# Design.net
KiCad netlist of a schematic drawn in EAGLE
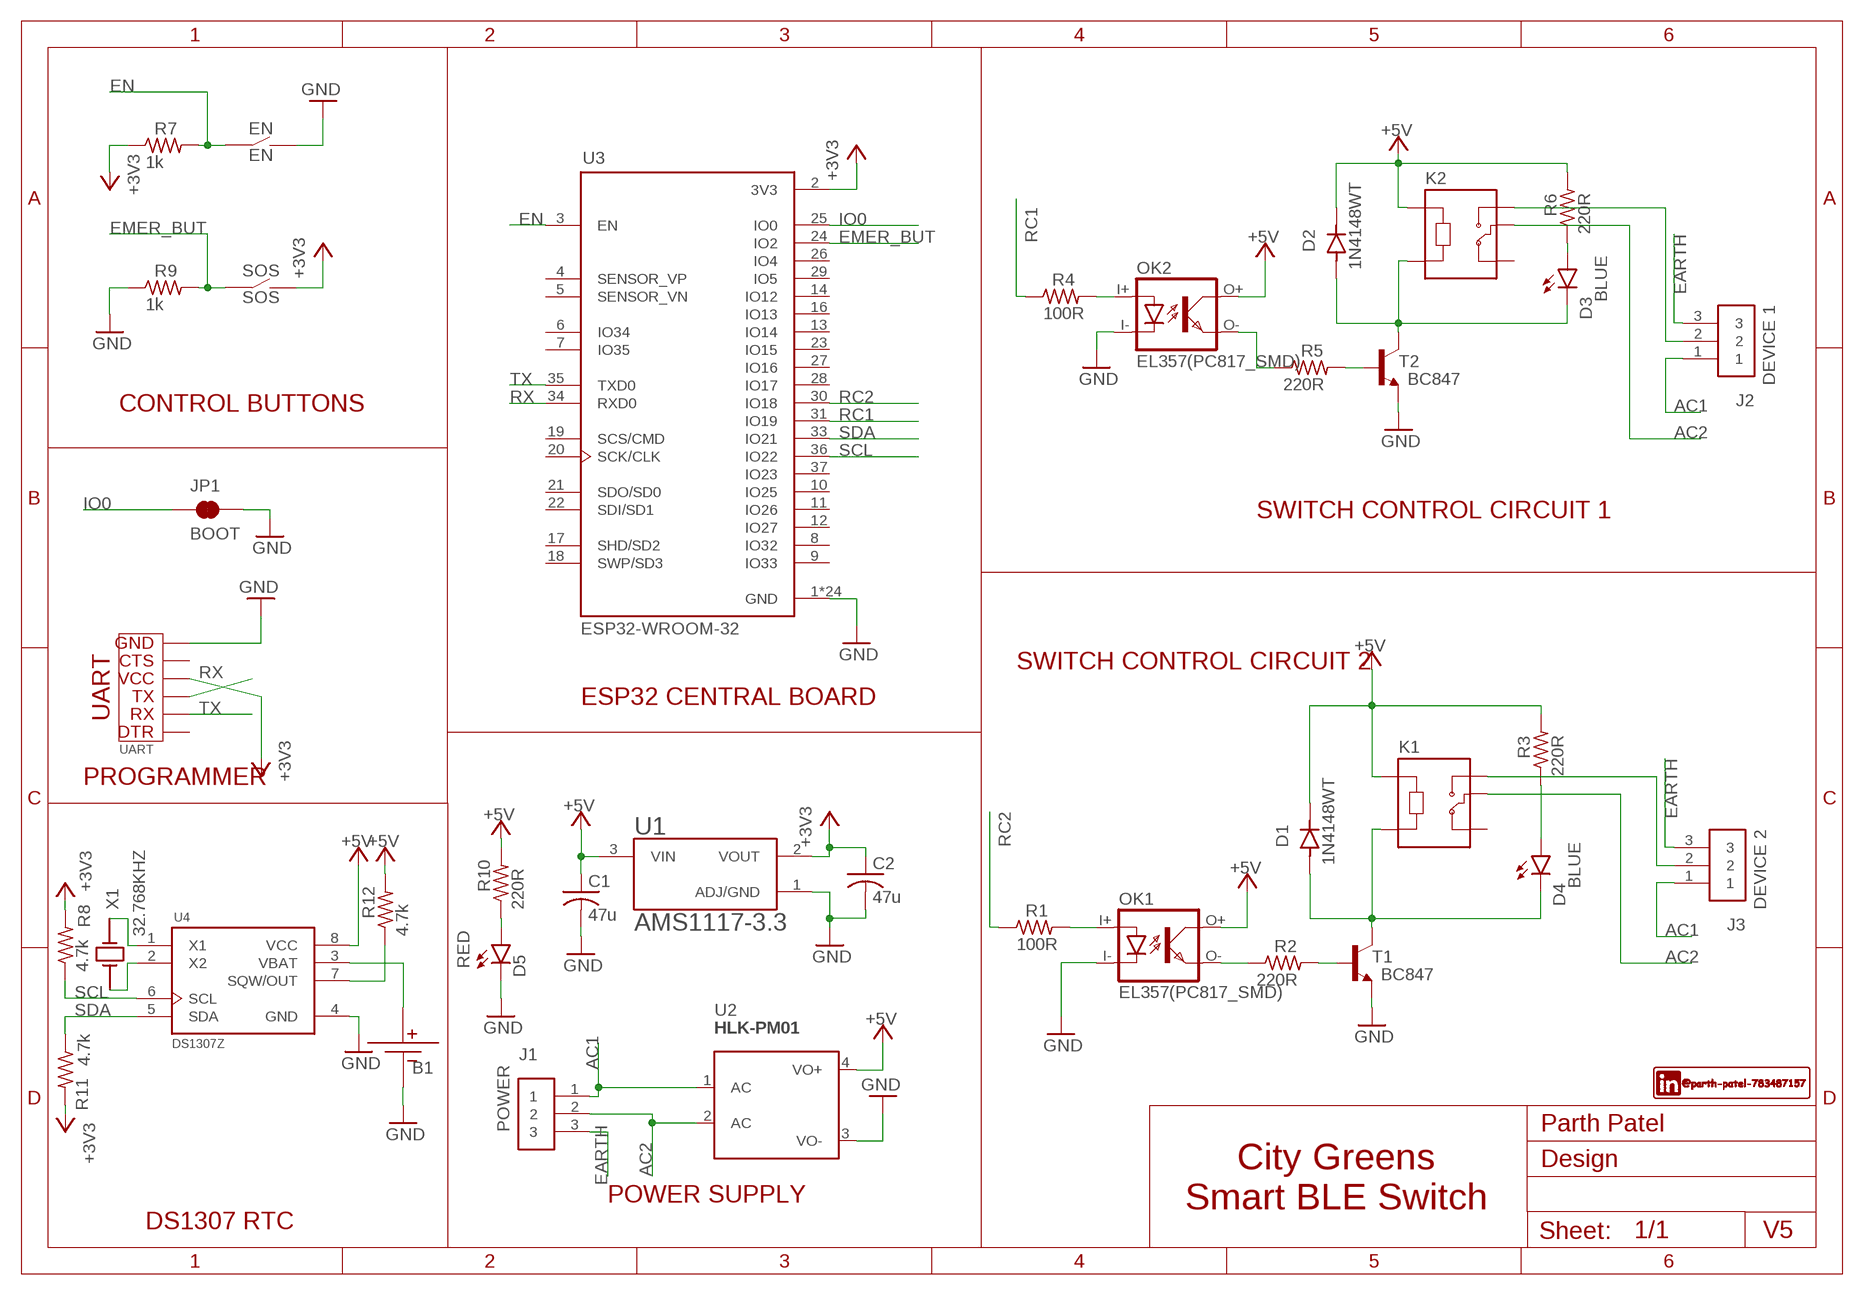
[diagram p0: schematic, sheet 1]

(export (version "E")
  (design (tool "Eeschema 10.0.6"))
  (components
    (comp (ref "B1")
      (value "CR3032-METAL")
      (footprint "eagle-import:CR2032-METAL")
      (libsource (lib "eagle-import") (part "CR3032-METAL"))
    )
    (comp (ref "C1")
      (value "47u")
      (footprint "eagle-import:C0805")
      (libsource (lib "eagle-import") (part "C-USC0805"))
    )
    (comp (ref "C2")
      (value "47u")
      (footprint "eagle-import:C0805")
      (libsource (lib "eagle-import") (part "C-USC0805"))
    )
    (comp (ref "D1")
      (value "1N4148WT")
      (footprint "eagle-import:SODFL1608X70N")
      (libsource (lib "eagle-import") (part "1N4148WT"))
    )
    (comp (ref "D2")
      (value "1N4148WT")
      (footprint "eagle-import:SODFL1608X70N")
      (fields (field (name "SPICEPREFIX") "D"))
      (libsource (lib "eagle-import") (part "1N4148WT"))
    )
    (comp (ref "D3")
      (value "BLUE")
      (footprint "eagle-import:CHIP-LED0603")
      (libsource (lib "eagle-import") (part "LEDCHIP-LED0603"))
    )
    (comp (ref "D4")
      (value "BLUE")
      (footprint "eagle-import:CHIP-LED0603")
      (libsource (lib "eagle-import") (part "LEDCHIP-LED0603"))
    )
    (comp (ref "D5")
      (value "RED")
      (footprint "eagle-import:CHIP-LED0603")
      (libsource (lib "eagle-import") (part "LEDCHIP-LED0603"))
    )
    (comp (ref "EN")
      (value "EN")
      (footprint "eagle-import:SMD-4.5X4.5-TACTILE-PUSH-BUTTON")
      (libsource (lib "eagle-import") (part "4.5X4.5-SMD-TACTILE-SWITCH"))
    )
    (comp (ref "J1")
      (value "POWER")
      (footprint "eagle-import:TERMINALBLOCK_PLUGGABLE-3-7.62MM")
      (fields
        (field (name "DIGIKEY_PART_NO") "732-2824-ND")
        (field (name "MANUFACTURER") "WURTH ELEKTRONIK")
        (field (name "MPN") "691311400103")
        (field (name "CREATED_BY") "PCBLayout.com")
      )
      (libsource (lib "eagle-import") (part "691311400103"))
    )
    (comp (ref "J2")
      (value "DEVICE 1")
      (footprint "eagle-import:TERMINALBLOCK_PLUGGABLE-3-7.62MM")
      (fields
        (field (name "DIGIKEY_PART_NO") "732-2824-ND")
        (field (name "MANUFACTURER") "WURTH ELEKTRONIK")
        (field (name "MPN") "691311400103")
        (field (name "CREATED_BY") "PCBLayout.com")
      )
      (libsource (lib "eagle-import") (part "691311400103"))
    )
    (comp (ref "J3")
      (value "DEVICE 2")
      (footprint "eagle-import:TERMINALBLOCK_PLUGGABLE-3-7.62MM")
      (fields
        (field (name "DIGIKEY_PART_NO") "732-2824-ND")
        (field (name "MANUFACTURER") "WURTH ELEKTRONIK")
        (field (name "MPN") "691311400103")
        (field (name "CREATED_BY") "PCBLayout.com")
      )
      (libsource (lib "eagle-import") (part "691311400103"))
    )
    (comp (ref "JP1")
      (value "BOOT")
      (footprint "eagle-import:SMT-JUMPER_2_NC_TRACE_SILK")
      (libsource (lib "eagle-import") (part "JUMPER-SMT_2_NC_TRACE_SILK"))
    )
    (comp (ref "K1")
      (value "SRD-05VDC-SL-C")
      (footprint "eagle-import:RELAY_SRD-05VDC-SL-C")
      (fields (field (name "MF") "Songle Relay"))
      (libsource (lib "eagle-import") (part "SRD-05VDC-SL-C"))
    )
    (comp (ref "K2")
      (value "SRD-05VDC-SL-C")
      (footprint "eagle-import:RELAY_SRD-05VDC-SL-C")
      (fields (field (name "MF") "Songle Relay"))
      (libsource (lib "eagle-import") (part "SRD-05VDC-SL-C"))
    )
    (comp (ref "OK1")
      (value "EL357(PC817_SMD)")
      (footprint "eagle-import:SOP254P715X240-4N")
      (libsource (lib "eagle-import") (part "EL357(PC817_SMD)"))
    )
    (comp (ref "OK2")
      (value "EL357(PC817_SMD)")
      (footprint "eagle-import:SOP254P715X240-4N")
      (libsource (lib "eagle-import") (part "EL357(PC817_SMD)"))
    )
    (comp (ref "R1")
      (value "100R")
      (footprint "eagle-import:R0805")
      (libsource (lib "eagle-import") (part "R-US_R0805"))
    )
    (comp (ref "R2")
      (value "220R")
      (footprint "eagle-import:R0805")
      (libsource (lib "eagle-import") (part "R-US_R0805"))
    )
    (comp (ref "R3")
      (value "220R")
      (footprint "eagle-import:R0805")
      (libsource (lib "eagle-import") (part "R-US_R0805"))
    )
    (comp (ref "R4")
      (value "100R")
      (footprint "eagle-import:R0805")
      (libsource (lib "eagle-import") (part "R-US_R0805"))
    )
    (comp (ref "R5")
      (value "220R")
      (footprint "eagle-import:R0805")
      (libsource (lib "eagle-import") (part "R-US_R0805"))
    )
    (comp (ref "R6")
      (value "220R")
      (footprint "eagle-import:R0805")
      (libsource (lib "eagle-import") (part "R-US_R0805"))
    )
    (comp (ref "R7")
      (value "1k")
      (footprint "eagle-import:R0805")
      (libsource (lib "eagle-import") (part "R-US_R0805"))
    )
    (comp (ref "R8")
      (value "4.7k")
      (footprint "eagle-import:R0805")
      (libsource (lib "eagle-import") (part "R-US_R0805"))
    )
    (comp (ref "R9")
      (value "1k")
      (footprint "eagle-import:R0805")
      (libsource (lib "eagle-import") (part "R-US_R0805"))
    )
    (comp (ref "R10")
      (value "220R")
      (footprint "eagle-import:R0805")
      (libsource (lib "eagle-import") (part "R-US_R0805"))
    )
    (comp (ref "R11")
      (value "4.7k")
      (footprint "eagle-import:R0805")
      (libsource (lib "eagle-import") (part "R-US_R0805"))
    )
    (comp (ref "R12")
      (value "4.7k")
      (footprint "eagle-import:R0805")
      (libsource (lib "eagle-import") (part "R-US_R0805"))
    )
    (comp (ref "SOS")
      (value "SOS")
      (footprint "eagle-import:SMD-4.5X4.5-TACTILE-PUSH-BUTTON")
      (libsource (lib "eagle-import") (part "4.5X4.5-SMD-TACTILE-SWITCH"))
    )
    (comp (ref "T1")
      (value "BC847")
      (footprint "eagle-import:SOT23")
      (libsource (lib "eagle-import") (part "BC847"))
    )
    (comp (ref "T2")
      (value "BC847")
      (footprint "eagle-import:SOT23")
      (libsource (lib "eagle-import") (part "BC847"))
    )
    (comp (ref "U1")
      (value "AMS1117-3.3")
      (footprint "eagle-import:SOT229P700X180-4N")
      (fields (field (name "MF") "AMD"))
      (libsource (lib "eagle-import") (part "AMS1117-3.3"))
    )
    (comp (ref "U2")
      (value "HLK-PM01")
      (footprint "eagle-import:HLK-PM01")
      (fields (field (name "MF") "Hi-link") (field (name "MP") "hlk-pm01"))
      (libsource (lib "eagle-import") (part "HLK-PM01"))
    )
    (comp (ref "U3")
      (value "ESP32-WROOM-32")
      (footprint "eagle-import:MODULE_ESP32-WROOM-32")
      (fields (field (name "MF") "Espressif Systems"))
      (libsource (lib "eagle-import") (part "ESP32-WROOM-32"))
    )
    (comp (ref "U4")
      (value "DS1307Z")
      (footprint "eagle-import:SOIC127P600X175-8N")
      (fields (field (name "MF") "Maxim Integrated"))
      (libsource (lib "eagle-import") (part "DS1307Z"))
    )
    (comp (ref "UART")
      (value "UART")
      (footprint "eagle-import:UART")
      (libsource (lib "eagle-import") (part "UART"))
    )
    (comp (ref "X1")
      (value "32.768KHZ")
      (footprint "eagle-import:XTAL_AB38T-32.768KHZ")
      (fields (field (name "MF") "Abracon") (field (name "MP") "AB38T-32.768KHZ"))
      (libsource (lib "eagle-import") (part "AB38T-32.768KHZ"))
    )
  )
  (nets
    (net (code "1") (name "+3V3") (class "Default")
      (node (ref "C2") (pin "1") (pinfunction "1_1") (pintype "passive"))
      (node (ref "R11") (pin "2") (pinfunction "2_2") (pintype "passive"))
      (node (ref "R7") (pin "1") (pinfunction "1_1") (pintype "passive"))
      (node (ref "R8") (pin "2") (pinfunction "2_2") (pintype "passive"))
      (node (ref "SOS") (pin "2.1") (pinfunction "S2_2.1") (pintype "bidirectional"))
      (node (ref "SOS") (pin "2.2") (pinfunction "S2_2.2") (pintype "bidirectional"))
      (node (ref "U1") (pin "2") (pinfunction "VOUT_2") (pintype "output"))
      (node (ref "U3") (pin "2") (pinfunction "3V3_2") (pintype "power_in"))
      (node (ref "UART") (pin "VCC") (pinfunction "VCC_VCC") (pintype "bidirectional"))
    )
    (net (code "2") (name "+5V") (class "Default")
      (node (ref "C1") (pin "1") (pinfunction "1_1") (pintype "passive"))
      (node (ref "D1") (pin "D+") (pinfunction "D+_D+") (pintype "passive"))
      (node (ref "D2") (pin "D+") (pinfunction "D+_D+") (pintype "passive"))
      (node (ref "K1") (pin "A1") (pinfunction "A1_A1") (pintype "passive"))
      (node (ref "K2") (pin "A1") (pinfunction "A1_A1") (pintype "passive"))
      (node (ref "OK1") (pin "O+") (pinfunction "O+_O+") (pintype "passive"))
      (node (ref "OK2") (pin "O+") (pinfunction "O+_O+") (pintype "passive"))
      (node (ref "R10") (pin "2") (pinfunction "2_2") (pintype "passive"))
      (node (ref "R12") (pin "2") (pinfunction "2_2") (pintype "passive"))
      (node (ref "R3") (pin "2") (pinfunction "2_2") (pintype "passive"))
      (node (ref "R6") (pin "2") (pinfunction "2_2") (pintype "passive"))
      (node (ref "U1") (pin "3") (pinfunction "VIN_3") (pintype "input"))
      (node (ref "U2") (pin "4") (pinfunction "VO+_4") (pintype "bidirectional"))
      (node (ref "U4") (pin "8") (pinfunction "VCC_8") (pintype "power_in"))
    )
    (net (code "3") (name "/AC1") (class "Default")
      (node (ref "J1") (pin "1") (pinfunction "1_1") (pintype "passive"))
      (node (ref "J2") (pin "1") (pinfunction "1_1") (pintype "passive"))
      (node (ref "J3") (pin "1") (pinfunction "1_1") (pintype "passive"))
      (node (ref "U2") (pin "1") (pinfunction "AC_1") (pintype "bidirectional"))
    )
    (net (code "4") (name "/AC2") (class "Default")
      (node (ref "J1") (pin "2") (pinfunction "2_2") (pintype "passive"))
      (node (ref "K1") (pin "COM") (pinfunction "COM_COM") (pintype "passive"))
      (node (ref "K2") (pin "COM") (pinfunction "COM_COM") (pintype "passive"))
      (node (ref "U2") (pin "2") (pinfunction "AC_2") (pintype "bidirectional"))
    )
    (net (code "5") (name "/EARTH") (class "Default")
      (node (ref "J1") (pin "3") (pinfunction "3_3") (pintype "passive"))
      (node (ref "J2") (pin "3") (pinfunction "3_3") (pintype "passive"))
      (node (ref "J3") (pin "3") (pinfunction "3_3") (pintype "passive"))
    )
    (net (code "6") (name "/EMER_BUT") (class "Default")
      (node (ref "R9") (pin "2") (pinfunction "2_2") (pintype "passive"))
      (node (ref "SOS") (pin "1.1") (pinfunction "S1_1.1") (pintype "bidirectional"))
      (node (ref "SOS") (pin "1.2") (pinfunction "S1_1.2") (pintype "bidirectional"))
      (node (ref "U3") (pin "24") (pinfunction "IO2_24") (pintype "bidirectional"))
    )
    (net (code "7") (name "/EN") (class "Default")
      (node (ref "EN") (pin "1.1") (pinfunction "S1_1.1") (pintype "bidirectional"))
      (node (ref "EN") (pin "1.2") (pinfunction "S1_1.2") (pintype "bidirectional"))
      (node (ref "R7") (pin "2") (pinfunction "2_2") (pintype "passive"))
      (node (ref "U3") (pin "3") (pinfunction "EN_3") (pintype "input"))
    )
    (net (code "8") (name "/IO0") (class "Default")
      (node (ref "JP1") (pin "1") (pinfunction "1_1") (pintype "passive"))
      (node (ref "U3") (pin "25") (pinfunction "IO0_25") (pintype "bidirectional"))
    )
    (net (code "9") (name "/RC1") (class "Default")
      (node (ref "R4") (pin "1") (pinfunction "1_1") (pintype "passive"))
      (node (ref "U3") (pin "31") (pinfunction "IO19_31") (pintype "bidirectional"))
    )
    (net (code "10") (name "/RC2") (class "Default")
      (node (ref "R1") (pin "1") (pinfunction "1_1") (pintype "passive"))
      (node (ref "U3") (pin "30") (pinfunction "IO18_30") (pintype "bidirectional"))
    )
    (net (code "11") (name "/RX") (class "Default")
      (node (ref "U3") (pin "34") (pinfunction "RXD0_34") (pintype "bidirectional"))
      (node (ref "UART") (pin "TX") (pinfunction "TX_TX") (pintype "bidirectional"))
    )
    (net (code "12") (name "/SCL") (class "Default")
      (node (ref "R8") (pin "1") (pinfunction "1_1") (pintype "passive"))
      (node (ref "U3") (pin "36") (pinfunction "IO22_36") (pintype "bidirectional"))
      (node (ref "U4") (pin "6") (pinfunction "SCL_6") (pintype "input"))
    )
    (net (code "13") (name "/SDA") (class "Default")
      (node (ref "R11") (pin "1") (pinfunction "1_1") (pintype "passive"))
      (node (ref "U3") (pin "33") (pinfunction "IO21_33") (pintype "bidirectional"))
      (node (ref "U4") (pin "5") (pinfunction "SDA_5") (pintype "bidirectional"))
    )
    (net (code "14") (name "/TX") (class "Default")
      (node (ref "U3") (pin "35") (pinfunction "TXD0_35") (pintype "bidirectional"))
      (node (ref "UART") (pin "RX") (pinfunction "RX_RX") (pintype "bidirectional"))
    )
    (net (code "15") (name "GND") (class "Default")
      (node (ref "B1") (pin "-VE1") (pinfunction "-VE_-VE1") (pintype "bidirectional"))
      (node (ref "B1") (pin "-VE2") (pinfunction "-VE_-VE2") (pintype "bidirectional"))
      (node (ref "C1") (pin "2") (pinfunction "2_2") (pintype "passive"))
      (node (ref "C2") (pin "2") (pinfunction "2_2") (pintype "passive"))
      (node (ref "D5") (pin "C") (pinfunction "C_C") (pintype "passive"))
      (node (ref "EN") (pin "2.1") (pinfunction "S2_2.1") (pintype "bidirectional"))
      (node (ref "EN") (pin "2.2") (pinfunction "S2_2.2") (pintype "bidirectional"))
      (node (ref "JP1") (pin "2") (pinfunction "2_2") (pintype "passive"))
      (node (ref "OK1") (pin "I-") (pinfunction "I-_I-") (pintype "passive"))
      (node (ref "OK2") (pin "I-") (pinfunction "I-_I-") (pintype "passive"))
      (node (ref "R9") (pin "1") (pinfunction "1_1") (pintype "passive"))
      (node (ref "T1") (pin "2") (pinfunction "E_2") (pintype "passive"))
      (node (ref "T2") (pin "2") (pinfunction "E_2") (pintype "passive"))
      (node (ref "U1") (pin "1") (pinfunction "ADJ/GND_1") (pintype "power_in"))
      (node (ref "U2") (pin "3") (pinfunction "VO-_3") (pintype "bidirectional"))
      (node (ref "U3") (pin "1") (pinfunction "GND_1") (pintype "power_in"))
      (node (ref "U3") (pin "15") (pinfunction "GND_15") (pintype "power_in"))
      (node (ref "U3") (pin "38") (pinfunction "GND_38") (pintype "power_in"))
      (node (ref "U3") (pin "39_1") (pinfunction "GND_39_1") (pintype "power_in"))
      (node (ref "U3") (pin "39_10") (pinfunction "GND_39_10") (pintype "power_in"))
      (node (ref "U3") (pin "39_11") (pinfunction "GND_39_11") (pintype "power_in"))
      (node (ref "U3") (pin "39_12") (pinfunction "GND_39_12") (pintype "power_in"))
      (node (ref "U3") (pin "39_13") (pinfunction "GND_39_13") (pintype "power_in"))
      (node (ref "U3") (pin "39_14") (pinfunction "GND_39_14") (pintype "power_in"))
      (node (ref "U3") (pin "39_15") (pinfunction "GND_39_15") (pintype "power_in"))
      (node (ref "U3") (pin "39_16") (pinfunction "GND_39_16") (pintype "power_in"))
      (node (ref "U3") (pin "39_17") (pinfunction "GND_39_17") (pintype "power_in"))
      (node (ref "U3") (pin "39_18") (pinfunction "GND_39_18") (pintype "power_in"))
      (node (ref "U3") (pin "39_19") (pinfunction "GND_39_19") (pintype "power_in"))
      (node (ref "U3") (pin "39_2") (pinfunction "GND_39_2") (pintype "power_in"))
      (node (ref "U3") (pin "39_20") (pinfunction "GND_39_20") (pintype "power_in"))
      (node (ref "U3") (pin "39_21") (pinfunction "GND_39_21") (pintype "power_in"))
      (node (ref "U3") (pin "39_3") (pinfunction "GND_39_3") (pintype "power_in"))
      (node (ref "U3") (pin "39_4") (pinfunction "GND_39_4") (pintype "power_in"))
      (node (ref "U3") (pin "39_5") (pinfunction "GND_39_5") (pintype "power_in"))
      (node (ref "U3") (pin "39_6") (pinfunction "GND_39_6") (pintype "power_in"))
      (node (ref "U3") (pin "39_7") (pinfunction "GND_39_7") (pintype "power_in"))
      (node (ref "U3") (pin "39_8") (pinfunction "GND_39_8") (pintype "power_in"))
      (node (ref "U3") (pin "39_9") (pinfunction "GND_39_9") (pintype "power_in"))
      (node (ref "U4") (pin "4") (pinfunction "GND_4") (pintype "power_in"))
      (node (ref "UART") (pin "GND") (pinfunction "GND_GND") (pintype "bidirectional"))
    )
    (net (code "16") (name "Net-(D3-PadA)") (class "Default")
      (node (ref "D3") (pin "A") (pinfunction "A_A") (pintype "passive"))
      (node (ref "R6") (pin "1") (pinfunction "1_1") (pintype "passive"))
    )
    (net (code "17") (name "Net-(D4-PadA)") (class "Default")
      (node (ref "D4") (pin "A") (pinfunction "A_A") (pintype "passive"))
      (node (ref "R3") (pin "1") (pinfunction "1_1") (pintype "passive"))
    )
    (net (code "18") (name "Net-(D5-PadA)") (class "Default")
      (node (ref "D5") (pin "A") (pinfunction "A_A") (pintype "passive"))
      (node (ref "R10") (pin "1") (pinfunction "1_1") (pintype "passive"))
    )
    (net (code "19") (name "Net-(J2-Pad2)") (class "Default")
      (node (ref "J2") (pin "2") (pinfunction "2_2") (pintype "passive"))
      (node (ref "K2") (pin "NO") (pinfunction "NO_NO") (pintype "passive"))
    )
    (net (code "20") (name "Net-(J3-Pad2)") (class "Default")
      (node (ref "J3") (pin "2") (pinfunction "2_2") (pintype "passive"))
      (node (ref "K1") (pin "NO") (pinfunction "NO_NO") (pintype "passive"))
    )
    (net (code "21") (name "Net-(OK1-PadI+)") (class "Default")
      (node (ref "OK1") (pin "I+") (pinfunction "I+_I+") (pintype "passive"))
      (node (ref "R1") (pin "2") (pinfunction "2_2") (pintype "passive"))
    )
    (net (code "22") (name "Net-(OK1-PadO-)") (class "Default")
      (node (ref "OK1") (pin "O-") (pinfunction "O-_O-") (pintype "passive"))
      (node (ref "R2") (pin "1") (pinfunction "1_1") (pintype "passive"))
    )
    (net (code "23") (name "Net-(OK2-PadI+)") (class "Default")
      (node (ref "OK2") (pin "I+") (pinfunction "I+_I+") (pintype "passive"))
      (node (ref "R4") (pin "2") (pinfunction "2_2") (pintype "passive"))
    )
    (net (code "24") (name "Net-(OK2-PadO-)") (class "Default")
      (node (ref "OK2") (pin "O-") (pinfunction "O-_O-") (pintype "passive"))
      (node (ref "R5") (pin "1") (pinfunction "1_1") (pintype "passive"))
    )
    (net (code "25") (name "Net-(T1-B)") (class "Default")
      (node (ref "R2") (pin "2") (pinfunction "2_2") (pintype "passive"))
      (node (ref "T1") (pin "1") (pinfunction "B_1") (pintype "passive"))
    )
    (net (code "26") (name "Net-(T1-C)") (class "Default")
      (node (ref "D1") (pin "D-") (pinfunction "D-_D-") (pintype "passive"))
      (node (ref "D4") (pin "C") (pinfunction "C_C") (pintype "passive"))
      (node (ref "K1") (pin "A2") (pinfunction "A2_A2") (pintype "passive"))
      (node (ref "T1") (pin "3") (pinfunction "C_3") (pintype "passive"))
    )
    (net (code "27") (name "Net-(T2-B)") (class "Default")
      (node (ref "R5") (pin "2") (pinfunction "2_2") (pintype "passive"))
      (node (ref "T2") (pin "1") (pinfunction "B_1") (pintype "passive"))
    )
    (net (code "28") (name "Net-(T2-C)") (class "Default")
      (node (ref "D2") (pin "D-") (pinfunction "D-_D-") (pintype "passive"))
      (node (ref "D3") (pin "C") (pinfunction "C_C") (pintype "passive"))
      (node (ref "K2") (pin "A2") (pinfunction "A2_A2") (pintype "passive"))
      (node (ref "T2") (pin "3") (pinfunction "C_3") (pintype "passive"))
    )
    (net (code "29") (name "Net-(U4-SQW{slash}OUT)") (class "Default")
      (node (ref "R12") (pin "1") (pinfunction "1_1") (pintype "passive"))
      (node (ref "U4") (pin "7") (pinfunction "SQW/OUT_7") (pintype "output"))
    )
    (net (code "30") (name "Net-(U4-VBAT)") (class "Default")
      (node (ref "B1") (pin "+VE") (pinfunction "+VE_+VE") (pintype "bidirectional"))
      (node (ref "U4") (pin "3") (pinfunction "VBAT_3") (pintype "power_in"))
    )
    (net (code "31") (name "Net-(U4-X1)") (class "Default")
      (node (ref "U4") (pin "1") (pinfunction "X1_1") (pintype "input"))
      (node (ref "X1") (pin "2") (pinfunction "2_2") (pintype "passive"))
    )
    (net (code "32") (name "Net-(U4-X2)") (class "Default")
      (node (ref "U4") (pin "2") (pinfunction "X2_2") (pintype "input"))
      (node (ref "X1") (pin "1") (pinfunction "1_1") (pintype "passive"))
    )
    (net (code "33") (name "unconnected-(K1-PadNC)") (class "Default")
      (node (ref "K1") (pin "NC") (pinfunction "NC_NC") (pintype "passive"))
    )
    (net (code "34") (name "unconnected-(K2-PadNC)") (class "Default")
      (node (ref "K2") (pin "NC") (pinfunction "NC_NC") (pintype "passive"))
    )
    (net (code "35") (name "unconnected-(U3-IO4-Pad26)") (class "Default")
      (node (ref "U3") (pin "26") (pinfunction "IO4_26") (pintype "bidirectional"))
    )
    (net (code "36") (name "unconnected-(U3-IO5-Pad29)") (class "Default")
      (node (ref "U3") (pin "29") (pinfunction "IO5_29") (pintype "bidirectional"))
    )
    (net (code "37") (name "unconnected-(U3-IO12-Pad14)") (class "Default")
      (node (ref "U3") (pin "14") (pinfunction "IO12_14") (pintype "bidirectional"))
    )
    (net (code "38") (name "unconnected-(U3-IO13-Pad16)") (class "Default")
      (node (ref "U3") (pin "16") (pinfunction "IO13_16") (pintype "bidirectional"))
    )
    (net (code "39") (name "unconnected-(U3-IO14-Pad13)") (class "Default")
      (node (ref "U3") (pin "13") (pinfunction "IO14_13") (pintype "bidirectional"))
    )
    (net (code "40") (name "unconnected-(U3-IO15-Pad23)") (class "Default")
      (node (ref "U3") (pin "23") (pinfunction "IO15_23") (pintype "bidirectional"))
    )
    (net (code "41") (name "unconnected-(U3-IO16-Pad27)") (class "Default")
      (node (ref "U3") (pin "27") (pinfunction "IO16_27") (pintype "bidirectional"))
    )
    (net (code "42") (name "unconnected-(U3-IO17-Pad28)") (class "Default")
      (node (ref "U3") (pin "28") (pinfunction "IO17_28") (pintype "bidirectional"))
    )
    (net (code "43") (name "unconnected-(U3-IO23-Pad37)") (class "Default")
      (node (ref "U3") (pin "37") (pinfunction "IO23_37") (pintype "bidirectional"))
    )
    (net (code "44") (name "unconnected-(U3-IO25-Pad10)") (class "Default")
      (node (ref "U3") (pin "10") (pinfunction "IO25_10") (pintype "bidirectional"))
    )
    (net (code "45") (name "unconnected-(U3-IO26-Pad11)") (class "Default")
      (node (ref "U3") (pin "11") (pinfunction "IO26_11") (pintype "bidirectional"))
    )
    (net (code "46") (name "unconnected-(U3-IO27-Pad12)") (class "Default")
      (node (ref "U3") (pin "12") (pinfunction "IO27_12") (pintype "bidirectional"))
    )
    (net (code "47") (name "unconnected-(U3-IO32-Pad8)") (class "Default")
      (node (ref "U3") (pin "8") (pinfunction "IO32_8") (pintype "bidirectional"))
    )
    (net (code "48") (name "unconnected-(U3-IO33-Pad9)") (class "Default")
      (node (ref "U3") (pin "9") (pinfunction "IO33_9") (pintype "bidirectional"))
    )
    (net (code "49") (name "unconnected-(U3-IO34-Pad6)") (class "Default")
      (node (ref "U3") (pin "6") (pinfunction "IO34_6") (pintype "input"))
    )
    (net (code "50") (name "unconnected-(U3-IO35-Pad7)") (class "Default")
      (node (ref "U3") (pin "7") (pinfunction "IO35_7") (pintype "input"))
    )
    (net (code "51") (name "unconnected-(U3-SCK{slash}CLK-Pad20)") (class "Default")
      (node (ref "U3") (pin "20") (pinfunction "SCK/CLK_20") (pintype "bidirectional"))
    )
    (net (code "52") (name "unconnected-(U3-SCS{slash}CMD-Pad19)") (class "Default")
      (node (ref "U3") (pin "19") (pinfunction "SCS/CMD_19") (pintype "bidirectional"))
    )
    (net (code "53") (name "unconnected-(U3-SDI{slash}SD1-Pad22)") (class "Default")
      (node (ref "U3") (pin "22") (pinfunction "SDI/SD1_22") (pintype "bidirectional"))
    )
    (net (code "54") (name "unconnected-(U3-SDO{slash}SD0-Pad21)") (class "Default")
      (node (ref "U3") (pin "21") (pinfunction "SDO/SD0_21") (pintype "bidirectional"))
    )
    (net (code "55") (name "unconnected-(U3-SENSOR_VN-Pad5)") (class "Default")
      (node (ref "U3") (pin "5") (pinfunction "SENSOR_VN_5") (pintype "input"))
    )
    (net (code "56") (name "unconnected-(U3-SENSOR_VP-Pad4)") (class "Default")
      (node (ref "U3") (pin "4") (pinfunction "SENSOR_VP_4") (pintype "input"))
    )
    (net (code "57") (name "unconnected-(U3-SHD{slash}SD2-Pad17)") (class "Default")
      (node (ref "U3") (pin "17") (pinfunction "SHD/SD2_17") (pintype "bidirectional"))
    )
    (net (code "58") (name "unconnected-(U3-SWP{slash}SD3-Pad18)") (class "Default")
      (node (ref "U3") (pin "18") (pinfunction "SWP/SD3_18") (pintype "bidirectional"))
    )
    (net (code "59") (name "unconnected-(UART-PadCTS)") (class "Default")
      (node (ref "UART") (pin "CTS") (pinfunction "CTS_CTS") (pintype "bidirectional"))
    )
    (net (code "60") (name "unconnected-(UART-PadDTR)") (class "Default")
      (node (ref "UART") (pin "DTR") (pinfunction "DTR_DTR") (pintype "bidirectional"))
    )
  )
)
